# 5_cyber60-alps_periferals.net
KiCad netlist of a schematic drawn in Altium Designer
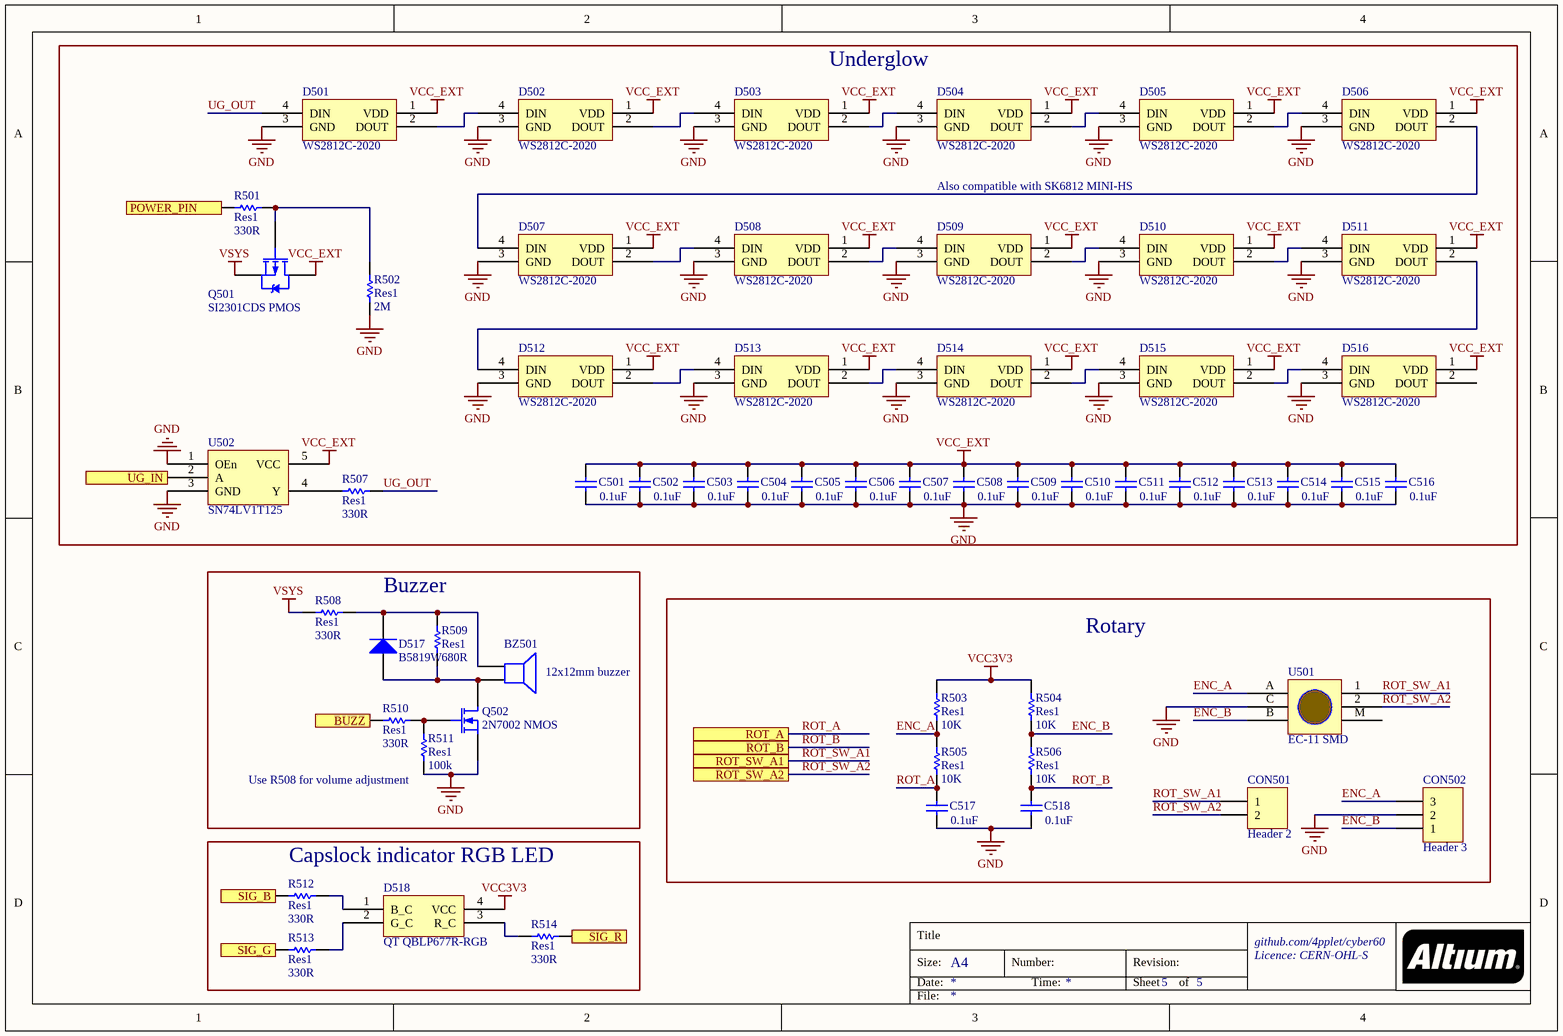
[diagram p0: 5_cyber60-alps_periferals.SchDoc]

(export (version "E")
  (design (tool "Eeschema 10.0.6"))
  (components
    (comp (ref "BZ501")
      (value "12x12mm buzzer")
      (footprint "buzzer 12x12")
      (description "Loudspeaker")
      (fields (field (name "LCSC PART #") "C409829") (field (name "MRF.PART") "YS-SBZ1230"))
      (libsource (lib "Miscellaneous Devices") (part "Speaker"))
    )
    (comp (ref "C501")
      (value "0.1uF")
      (footprint "C0603[1608]")
      (description "Capacitor")
      (fields (field (name "MFG") "KEMET") (field (name "LCSC PART #") "C14663"))
      (libsource (lib "Miscellaneous Devices") (part "Cap"))
    )
    (comp (ref "C502")
      (value "0.1uF")
      (footprint "C0603[1608]")
      (description "Capacitor")
      (fields (field (name "MFG") "KEMET") (field (name "LCSC PART #") "C14663"))
      (libsource (lib "Miscellaneous Devices") (part "Cap"))
    )
    (comp (ref "C503")
      (value "0.1uF")
      (footprint "C0603[1608]")
      (description "Capacitor")
      (fields (field (name "MFG") "KEMET") (field (name "LCSC PART #") "C14663"))
      (libsource (lib "Miscellaneous Devices") (part "Cap"))
    )
    (comp (ref "C504")
      (value "0.1uF")
      (footprint "C0603[1608]")
      (description "Capacitor")
      (fields (field (name "MFG") "KEMET") (field (name "LCSC PART #") "C14663"))
      (libsource (lib "Miscellaneous Devices") (part "Cap"))
    )
    (comp (ref "C505")
      (value "0.1uF")
      (footprint "C0603[1608]")
      (description "Capacitor")
      (fields (field (name "MFG") "KEMET") (field (name "LCSC PART #") "C14663"))
      (libsource (lib "Miscellaneous Devices") (part "Cap"))
    )
    (comp (ref "C506")
      (value "0.1uF")
      (footprint "C0603[1608]")
      (description "Capacitor")
      (fields (field (name "MFG") "KEMET") (field (name "LCSC PART #") "C14663"))
      (libsource (lib "Miscellaneous Devices") (part "Cap"))
    )
    (comp (ref "C507")
      (value "0.1uF")
      (footprint "C0603[1608]")
      (description "Capacitor")
      (fields (field (name "MFG") "KEMET") (field (name "LCSC PART #") "C14663"))
      (libsource (lib "Miscellaneous Devices") (part "Cap"))
    )
    (comp (ref "C508")
      (value "0.1uF")
      (footprint "C0603[1608]")
      (description "Capacitor")
      (fields (field (name "MFG") "KEMET") (field (name "LCSC PART #") "C14663"))
      (libsource (lib "Miscellaneous Devices") (part "Cap"))
    )
    (comp (ref "C509")
      (value "0.1uF")
      (footprint "C0603[1608]")
      (description "Capacitor")
      (fields (field (name "MFG") "KEMET") (field (name "LCSC PART #") "C14663"))
      (libsource (lib "Miscellaneous Devices") (part "Cap"))
    )
    (comp (ref "C510")
      (value "0.1uF")
      (footprint "C0603[1608]")
      (description "Capacitor")
      (fields (field (name "MFG") "KEMET") (field (name "LCSC PART #") "C14663"))
      (libsource (lib "Miscellaneous Devices") (part "Cap"))
    )
    (comp (ref "C511")
      (value "0.1uF")
      (footprint "C0603[1608]")
      (description "Capacitor")
      (fields (field (name "MFG") "KEMET") (field (name "LCSC PART #") "C14663"))
      (libsource (lib "Miscellaneous Devices") (part "Cap"))
    )
    (comp (ref "C512")
      (value "0.1uF")
      (footprint "C0603[1608]")
      (description "Capacitor")
      (fields (field (name "MFG") "KEMET") (field (name "LCSC PART #") "C14663"))
      (libsource (lib "Miscellaneous Devices") (part "Cap"))
    )
    (comp (ref "C513")
      (value "0.1uF")
      (footprint "C0603[1608]")
      (description "Capacitor")
      (fields (field (name "MFG") "KEMET") (field (name "LCSC PART #") "C14663"))
      (libsource (lib "Miscellaneous Devices") (part "Cap"))
    )
    (comp (ref "C514")
      (value "0.1uF")
      (footprint "C0603[1608]")
      (description "Capacitor")
      (fields (field (name "MFG") "KEMET") (field (name "LCSC PART #") "C14663"))
      (libsource (lib "Miscellaneous Devices") (part "Cap"))
    )
    (comp (ref "C515")
      (value "0.1uF")
      (footprint "C0603[1608]")
      (description "Capacitor")
      (fields (field (name "MFG") "KEMET") (field (name "LCSC PART #") "C14663"))
      (libsource (lib "Miscellaneous Devices") (part "Cap"))
    )
    (comp (ref "C516")
      (value "0.1uF")
      (footprint "C0603[1608]")
      (description "Capacitor")
      (fields (field (name "MFG") "KEMET") (field (name "LCSC PART #") "C14663"))
      (libsource (lib "Miscellaneous Devices") (part "Cap"))
    )
    (comp (ref "C517")
      (value "0.1uF")
      (footprint "C0603[1608]")
      (description "Capacitor")
      (fields (field (name "MFG") "KEMET") (field (name "LCSC PART #") "C14663"))
      (libsource (lib "Miscellaneous Devices") (part "Cap"))
    )
    (comp (ref "C518")
      (value "0.1uF")
      (footprint "C0603[1608]")
      (description "Capacitor")
      (fields (field (name "MFG") "KEMET") (field (name "LCSC PART #") "C14663"))
      (libsource (lib "Miscellaneous Devices") (part "Cap"))
    )
    (comp (ref "CON501")
      (value "Header 2")
      (footprint "HDR1X2")
      (description "Header, 2-Pin")
      (libsource (lib "Miscellaneous Connectors") (part "Header 2"))
    )
    (comp (ref "CON502")
      (value "Header 3")
      (footprint "HDR1X3")
      (description "Header, 3-Pin")
      (libsource (lib "Miscellaneous Connectors") (part "Header 3"))
    )
    (comp (ref "D501")
      (value "WS2812C-2020")
      (footprint "WS2812B - 2020")
      (fields (field (name "LCSC PART #") "C965556"))
      (libsource (lib "Keebs") (part "WS2812B"))
    )
    (comp (ref "D502")
      (value "WS2812C-2020")
      (footprint "WS2812B - 2020")
      (fields (field (name "LCSC PART #") "C965556"))
      (libsource (lib "Keebs") (part "WS2812B"))
    )
    (comp (ref "D503")
      (value "WS2812C-2020")
      (footprint "WS2812B - 2020")
      (fields (field (name "LCSC PART #") "C965556"))
      (libsource (lib "Keebs") (part "WS2812B"))
    )
    (comp (ref "D504")
      (value "WS2812C-2020")
      (footprint "WS2812B - 2020")
      (fields (field (name "LCSC PART #") "C965556"))
      (libsource (lib "Keebs") (part "WS2812B"))
    )
    (comp (ref "D505")
      (value "WS2812C-2020")
      (footprint "WS2812B - 2020")
      (fields (field (name "LCSC PART #") "C965556"))
      (libsource (lib "Keebs") (part "WS2812B"))
    )
    (comp (ref "D506")
      (value "WS2812C-2020")
      (footprint "WS2812B - 2020")
      (fields (field (name "LCSC PART #") "C965556"))
      (libsource (lib "Keebs") (part "WS2812B"))
    )
    (comp (ref "D507")
      (value "WS2812C-2020")
      (footprint "WS2812B - 2020")
      (fields (field (name "LCSC PART #") "C965556"))
      (libsource (lib "Keebs") (part "WS2812B"))
    )
    (comp (ref "D508")
      (value "WS2812C-2020")
      (footprint "WS2812B - 2020")
      (fields (field (name "LCSC PART #") "C965556"))
      (libsource (lib "Keebs") (part "WS2812B"))
    )
    (comp (ref "D509")
      (value "WS2812C-2020")
      (footprint "WS2812B - 2020")
      (fields (field (name "LCSC PART #") "C965556"))
      (libsource (lib "Keebs") (part "WS2812B"))
    )
    (comp (ref "D510")
      (value "WS2812C-2020")
      (footprint "WS2812B - 2020")
      (fields (field (name "LCSC PART #") "C965556"))
      (libsource (lib "Keebs") (part "WS2812B"))
    )
    (comp (ref "D511")
      (value "WS2812C-2020")
      (footprint "WS2812B - 2020")
      (fields (field (name "LCSC PART #") "C965556"))
      (libsource (lib "Keebs") (part "WS2812B"))
    )
    (comp (ref "D512")
      (value "WS2812C-2020")
      (footprint "WS2812B - 2020")
      (fields (field (name "LCSC PART #") "C965556"))
      (libsource (lib "Keebs") (part "WS2812B"))
    )
    (comp (ref "D513")
      (value "WS2812C-2020")
      (footprint "WS2812B - 2020")
      (fields (field (name "LCSC PART #") "C965556"))
      (libsource (lib "Keebs") (part "WS2812B"))
    )
    (comp (ref "D514")
      (value "WS2812C-2020")
      (footprint "WS2812B - 2020")
      (fields (field (name "LCSC PART #") "C965556"))
      (libsource (lib "Keebs") (part "WS2812B"))
    )
    (comp (ref "D515")
      (value "WS2812C-2020")
      (footprint "WS2812B - 2020")
      (fields (field (name "LCSC PART #") "C965556"))
      (libsource (lib "Keebs") (part "WS2812B"))
    )
    (comp (ref "D516")
      (value "WS2812C-2020")
      (footprint "WS2812B - 2020")
      (fields (field (name "LCSC PART #") "C965556"))
      (libsource (lib "Keebs") (part "WS2812B"))
    )
    (comp (ref "D517")
      (value "B5819W")
      (footprint "SOD-123")
      (description "Default Diode")
      (fields (field (name "LCSC PART #") "C8598"))
      (libsource (lib "Miscellaneous Devices") (part "Diode"))
    )
    (comp (ref "D518")
      (value "QT QBLP677R-RGB")
      (footprint "QT QBLP677R-RGB")
      (description "RGB LED")
      (fields (field (name "MFG") "QT Brightek (QTB)"))
      (libsource (lib "Keebs") (part "QT QBLP677R-RGB"))
    )
    (comp (ref "Q501")
      (value "SI2301CDS PMOS")
      (footprint "SOT-23-3")
      (description "P-Channel Power MOSFET")
      (fields (field (name "MRF.PART") "SI2301CDS-T1-GE3") (field (name "LCSC PART #") "C10487"))
      (libsource (lib "Miscellaneous Devices") (part "PMOS-2"))
    )
    (comp (ref "Q502")
      (value "2N7002 NMOS")
      (footprint "SOT-23-3")
      (description "N-Channel MOSFET")
      (fields (field (name "LCSC PART #") "C8545") (field (name "MRF.PART") "2N7002"))
      (libsource (lib "Miscellaneous Devices") (part "MOSFET-N"))
    )
    (comp (ref "R501")
      (value "Res1")
      (footprint "R0603[1608]")
      (description "Resistor")
      (fields
        (field (name "ALTIUM_VALUE") "330R")
        (field (name "LCSC PART #") "C23138")
        (field (name "MRF.PART") "0603WAF3300T5E")
      )
      (libsource (lib "Miscellaneous Devices") (part "Res1"))
    )
    (comp (ref "R502")
      (value "Res1")
      (footprint "R0603[1608]")
      (description "Resistor")
      (fields
        (field (name "ALTIUM_VALUE") "2M")
        (field (name "MRF.PART") "0603WAF2004T5E")
        (field (name "LCSC PART #") "C22976")
      )
      (libsource (lib "Miscellaneous Devices") (part "Res1"))
    )
    (comp (ref "R503")
      (value "Res1")
      (footprint "R0603[1608]")
      (description "Resistor")
      (fields
        (field (name "ALTIUM_VALUE") "10K")
        (field (name "MRF.PART") "0603WAF1002T5E")
        (field (name "LCSC PART #") "C25804")
      )
      (libsource (lib "Miscellaneous Devices") (part "Res1"))
    )
    (comp (ref "R504")
      (value "Res1")
      (footprint "R0603[1608]")
      (description "Resistor")
      (fields
        (field (name "ALTIUM_VALUE") "10K")
        (field (name "MRF.PART") "0603WAF1002T5E")
        (field (name "LCSC PART #") "C25804")
      )
      (libsource (lib "Miscellaneous Devices") (part "Res1"))
    )
    (comp (ref "R505")
      (value "Res1")
      (footprint "R0603[1608]")
      (description "Resistor")
      (fields
        (field (name "ALTIUM_VALUE") "10K")
        (field (name "MRF.PART") "0603WAF1002T5E")
        (field (name "LCSC PART #") "C25804")
      )
      (libsource (lib "Miscellaneous Devices") (part "Res1"))
    )
    (comp (ref "R506")
      (value "Res1")
      (footprint "R0603[1608]")
      (description "Resistor")
      (fields
        (field (name "ALTIUM_VALUE") "10K")
        (field (name "MRF.PART") "0603WAF1002T5E")
        (field (name "LCSC PART #") "C25804")
      )
      (libsource (lib "Miscellaneous Devices") (part "Res1"))
    )
    (comp (ref "R507")
      (value "Res1")
      (footprint "R0603[1608]")
      (description "Resistor")
      (fields
        (field (name "ALTIUM_VALUE") "330R")
        (field (name "LCSC PART #") "C23138")
        (field (name "MRF.PART") "0603WAF3300T5E")
      )
      (libsource (lib "Miscellaneous Devices") (part "Res1"))
    )
    (comp (ref "R508")
      (value "Res1")
      (footprint "R0603[1608]")
      (description "Resistor")
      (fields
        (field (name "ALTIUM_VALUE") "330R")
        (field (name "LCSC PART #") "C23138")
        (field (name "MRF.PART") "0603WAF3300T5E")
      )
      (libsource (lib "Miscellaneous Devices") (part "Res1"))
    )
    (comp (ref "R509")
      (value "Res1")
      (footprint "R0603[1608]")
      (description "Resistor")
      (fields
        (field (name "ALTIUM_VALUE") "680R")
        (field (name "MRF.PART") "0603WAF6800T5E")
        (field (name "LCSC PART #") "C23228")
      )
      (libsource (lib "Miscellaneous Devices") (part "Res1"))
    )
    (comp (ref "R510")
      (value "Res1")
      (footprint "R0603[1608]")
      (description "Resistor")
      (fields
        (field (name "ALTIUM_VALUE") "330R")
        (field (name "LCSC PART #") "C23138")
        (field (name "MRF.PART") "0603WAF3300T5E")
      )
      (libsource (lib "Miscellaneous Devices") (part "Res1"))
    )
    (comp (ref "R511")
      (value "Res1")
      (footprint "R0603[1608]")
      (description "Resistor")
      (fields
        (field (name "ALTIUM_VALUE") "100k")
        (field (name "MRF.PART") "0603WAF1003T5E")
        (field (name "LCSC PART #") "C25803")
      )
      (libsource (lib "Miscellaneous Devices") (part "Res1"))
    )
    (comp (ref "R512")
      (value "Res1")
      (footprint "R0603[1608]")
      (description "Resistor")
      (fields
        (field (name "ALTIUM_VALUE") "330R")
        (field (name "LCSC PART #") "C23138")
        (field (name "MRF.PART") "0603WAF3300T5E")
      )
      (libsource (lib "Miscellaneous Devices") (part "Res1"))
    )
    (comp (ref "R513")
      (value "Res1")
      (footprint "R0603[1608]")
      (description "Resistor")
      (fields
        (field (name "ALTIUM_VALUE") "330R")
        (field (name "LCSC PART #") "C23138")
        (field (name "MRF.PART") "0603WAF3300T5E")
      )
      (libsource (lib "Miscellaneous Devices") (part "Res1"))
    )
    (comp (ref "R514")
      (value "Res1")
      (footprint "R0603[1608]")
      (description "Resistor")
      (fields
        (field (name "ALTIUM_VALUE") "330R")
        (field (name "LCSC PART #") "C23138")
        (field (name "MRF.PART") "0603WAF3300T5E")
      )
      (libsource (lib "Miscellaneous Devices") (part "Res1"))
    )
    (comp (ref "U501") (value "EC-11 SMD") (footprint "EC11-SMD") (libsource (lib "Keebs") (part "EC-11")))
    (comp (ref "U502")
      (value "SN74LV1T125")
      (footprint "SOT-23-5")
      (description "SN74LV1T125 or SN74LV1T34. Connect OE to GND")
      (fields (field (name "LCSC PART #") "C473338") (field (name "MRF.PART") "SN74LV1T125DBVR"))
      (libsource (lib "Keebs") (part "SN74LV1T125"))
    )
  )
  (nets
    (net (code "1") (name "/BUZZ") (class "Default")
      (node (ref "R510") (pin "2") (pinfunction "2_2") (pintype "passive"))
    )
    (net (code "2") (name "/ENC_A") (class "Default")
      (node (ref "CON502") (pin "3") (pinfunction "3_3") (pintype "passive"))
      (node (ref "R503") (pin "2") (pinfunction "2_2") (pintype "passive"))
      (node (ref "R505") (pin "1") (pinfunction "1_1") (pintype "passive"))
      (node (ref "U501") (pin "A") (pinfunction "B_A") (pintype "passive"))
    )
    (net (code "3") (name "/ENC_B") (class "Default")
      (node (ref "CON502") (pin "1") (pinfunction "1_1") (pintype "passive"))
      (node (ref "R504") (pin "2") (pinfunction "2_2") (pintype "passive"))
      (node (ref "R506") (pin "1") (pinfunction "1_1") (pintype "passive"))
      (node (ref "U501") (pin "B") (pinfunction "B_B") (pintype "passive"))
    )
    (net (code "4") (name "/POWER_PIN") (class "Default")
      (node (ref "R501") (pin "1") (pinfunction "1_1") (pintype "passive"))
    )
    (net (code "5") (name "/ROT_A") (class "Default")
      (node (ref "C517") (pin "2") (pinfunction "2_2") (pintype "passive"))
      (node (ref "R505") (pin "2") (pinfunction "2_2") (pintype "passive"))
    )
    (net (code "6") (name "/ROT_B") (class "Default")
      (node (ref "C518") (pin "2") (pinfunction "2_2") (pintype "passive"))
      (node (ref "R506") (pin "2") (pinfunction "2_2") (pintype "passive"))
    )
    (net (code "7") (name "/ROT_SW_A1") (class "Default")
      (node (ref "CON501") (pin "1") (pinfunction "1_1") (pintype "passive"))
      (node (ref "U501") (pin "1") (pinfunction "1_1") (pintype "passive"))
    )
    (net (code "8") (name "/ROT_SW_A2") (class "Default")
      (node (ref "CON501") (pin "2") (pinfunction "2_2") (pintype "passive"))
      (node (ref "U501") (pin "2") (pinfunction "2_2") (pintype "passive"))
    )
    (net (code "9") (name "/SIG_B") (class "Default")
      (node (ref "R512") (pin "2") (pinfunction "2_2") (pintype "passive"))
    )
    (net (code "10") (name "/SIG_G") (class "Default")
      (node (ref "R513") (pin "2") (pinfunction "2_2") (pintype "passive"))
    )
    (net (code "11") (name "/SIG_R") (class "Default")
      (node (ref "R514") (pin "1") (pinfunction "1_1") (pintype "passive"))
    )
    (net (code "12") (name "/UG_IN") (class "Default")
      (node (ref "U502") (pin "2") (pinfunction "A_2") (pintype "passive"))
    )
    (net (code "13") (name "/UG_OUT") (class "Default")
      (node (ref "D501") (pin "4") (pinfunction "DIN_4") (pintype "passive"))
      (node (ref "R507") (pin "1") (pinfunction "1_1") (pintype "passive"))
    )
    (net (code "14") (name "GND") (class "Default")
      (node (ref "C501") (pin "1") (pinfunction "1_1") (pintype "passive"))
      (node (ref "C502") (pin "1") (pinfunction "1_1") (pintype "passive"))
      (node (ref "C503") (pin "1") (pinfunction "1_1") (pintype "passive"))
      (node (ref "C504") (pin "1") (pinfunction "1_1") (pintype "passive"))
      (node (ref "C505") (pin "1") (pinfunction "1_1") (pintype "passive"))
      (node (ref "C506") (pin "1") (pinfunction "1_1") (pintype "passive"))
      (node (ref "C507") (pin "1") (pinfunction "1_1") (pintype "passive"))
      (node (ref "C508") (pin "1") (pinfunction "1_1") (pintype "passive"))
      (node (ref "C509") (pin "1") (pinfunction "1_1") (pintype "passive"))
      (node (ref "C510") (pin "1") (pinfunction "1_1") (pintype "passive"))
      (node (ref "C511") (pin "1") (pinfunction "1_1") (pintype "passive"))
      (node (ref "C512") (pin "1") (pinfunction "1_1") (pintype "passive"))
      (node (ref "C513") (pin "1") (pinfunction "1_1") (pintype "passive"))
      (node (ref "C514") (pin "1") (pinfunction "1_1") (pintype "passive"))
      (node (ref "C515") (pin "1") (pinfunction "1_1") (pintype "passive"))
      (node (ref "C516") (pin "1") (pinfunction "1_1") (pintype "passive"))
      (node (ref "C517") (pin "1") (pinfunction "1_1") (pintype "passive"))
      (node (ref "C518") (pin "1") (pinfunction "1_1") (pintype "passive"))
      (node (ref "CON502") (pin "2") (pinfunction "2_2") (pintype "passive"))
      (node (ref "D501") (pin "3") (pinfunction "GND_3") (pintype "passive"))
      (node (ref "D502") (pin "3") (pinfunction "GND_3") (pintype "passive"))
      (node (ref "D503") (pin "3") (pinfunction "GND_3") (pintype "passive"))
      (node (ref "D504") (pin "3") (pinfunction "GND_3") (pintype "passive"))
      (node (ref "D505") (pin "3") (pinfunction "GND_3") (pintype "passive"))
      (node (ref "D506") (pin "3") (pinfunction "GND_3") (pintype "passive"))
      (node (ref "D507") (pin "3") (pinfunction "GND_3") (pintype "passive"))
      (node (ref "D508") (pin "3") (pinfunction "GND_3") (pintype "passive"))
      (node (ref "D509") (pin "3") (pinfunction "GND_3") (pintype "passive"))
      (node (ref "D510") (pin "3") (pinfunction "GND_3") (pintype "passive"))
      (node (ref "D511") (pin "3") (pinfunction "GND_3") (pintype "passive"))
      (node (ref "D512") (pin "3") (pinfunction "GND_3") (pintype "passive"))
      (node (ref "D513") (pin "3") (pinfunction "GND_3") (pintype "passive"))
      (node (ref "D514") (pin "3") (pinfunction "GND_3") (pintype "passive"))
      (node (ref "D515") (pin "3") (pinfunction "GND_3") (pintype "passive"))
      (node (ref "D516") (pin "3") (pinfunction "GND_3") (pintype "passive"))
      (node (ref "Q502") (pin "2") (pinfunction "S_2") (pintype "passive"))
      (node (ref "R502") (pin "1") (pinfunction "1_1") (pintype "passive"))
      (node (ref "R511") (pin "2") (pinfunction "2_2") (pintype "passive"))
      (node (ref "U501") (pin "C") (pinfunction "C_C") (pintype "passive"))
      (node (ref "U502") (pin "1") (pinfunction "OEn_1") (pintype "passive"))
      (node (ref "U502") (pin "3") (pinfunction "GND_3") (pintype "passive"))
    )
    (net (code "15") (name "Net-(D501-DOUT)") (class "Default")
      (node (ref "D501") (pin "2") (pinfunction "DOUT_2") (pintype "passive"))
      (node (ref "D502") (pin "4") (pinfunction "DIN_4") (pintype "passive"))
    )
    (net (code "16") (name "Net-(D502-DOUT)") (class "Default")
      (node (ref "D502") (pin "2") (pinfunction "DOUT_2") (pintype "passive"))
      (node (ref "D503") (pin "4") (pinfunction "DIN_4") (pintype "passive"))
    )
    (net (code "17") (name "Net-(D503-DOUT)") (class "Default")
      (node (ref "D503") (pin "2") (pinfunction "DOUT_2") (pintype "passive"))
      (node (ref "D504") (pin "4") (pinfunction "DIN_4") (pintype "passive"))
    )
    (net (code "18") (name "Net-(D504-DOUT)") (class "Default")
      (node (ref "D504") (pin "2") (pinfunction "DOUT_2") (pintype "passive"))
      (node (ref "D505") (pin "4") (pinfunction "DIN_4") (pintype "passive"))
    )
    (net (code "19") (name "Net-(D505-DOUT)") (class "Default")
      (node (ref "D505") (pin "2") (pinfunction "DOUT_2") (pintype "passive"))
      (node (ref "D506") (pin "4") (pinfunction "DIN_4") (pintype "passive"))
    )
    (net (code "20") (name "Net-(D506-DOUT)") (class "Default")
      (node (ref "D506") (pin "2") (pinfunction "DOUT_2") (pintype "passive"))
      (node (ref "D507") (pin "4") (pinfunction "DIN_4") (pintype "passive"))
    )
    (net (code "21") (name "Net-(D507-DOUT)") (class "Default")
      (node (ref "D507") (pin "2") (pinfunction "DOUT_2") (pintype "passive"))
      (node (ref "D508") (pin "4") (pinfunction "DIN_4") (pintype "passive"))
    )
    (net (code "22") (name "Net-(D508-DOUT)") (class "Default")
      (node (ref "D508") (pin "2") (pinfunction "DOUT_2") (pintype "passive"))
      (node (ref "D509") (pin "4") (pinfunction "DIN_4") (pintype "passive"))
    )
    (net (code "23") (name "Net-(D509-DOUT)") (class "Default")
      (node (ref "D509") (pin "2") (pinfunction "DOUT_2") (pintype "passive"))
      (node (ref "D510") (pin "4") (pinfunction "DIN_4") (pintype "passive"))
    )
    (net (code "24") (name "Net-(D510-DOUT)") (class "Default")
      (node (ref "D510") (pin "2") (pinfunction "DOUT_2") (pintype "passive"))
      (node (ref "D511") (pin "4") (pinfunction "DIN_4") (pintype "passive"))
    )
    (net (code "25") (name "Net-(D511-DOUT)") (class "Default")
      (node (ref "D511") (pin "2") (pinfunction "DOUT_2") (pintype "passive"))
      (node (ref "D512") (pin "4") (pinfunction "DIN_4") (pintype "passive"))
    )
    (net (code "26") (name "Net-(D512-DOUT)") (class "Default")
      (node (ref "D512") (pin "2") (pinfunction "DOUT_2") (pintype "passive"))
      (node (ref "D513") (pin "4") (pinfunction "DIN_4") (pintype "passive"))
    )
    (net (code "27") (name "Net-(D513-DOUT)") (class "Default")
      (node (ref "D513") (pin "2") (pinfunction "DOUT_2") (pintype "passive"))
      (node (ref "D514") (pin "4") (pinfunction "DIN_4") (pintype "passive"))
    )
    (net (code "28") (name "Net-(D514-DOUT)") (class "Default")
      (node (ref "D514") (pin "2") (pinfunction "DOUT_2") (pintype "passive"))
      (node (ref "D515") (pin "4") (pinfunction "DIN_4") (pintype "passive"))
    )
    (net (code "29") (name "Net-(D515-DOUT)") (class "Default")
      (node (ref "D515") (pin "2") (pinfunction "DOUT_2") (pintype "passive"))
      (node (ref "D516") (pin "4") (pinfunction "DIN_4") (pintype "passive"))
    )
    (net (code "30") (name "Net-(D517-A)") (class "Default")
      (node (ref "BZ501") (pin "2") (pinfunction "2_2") (pintype "passive"))
      (node (ref "D517") (pin "1") (pinfunction "A_1") (pintype "passive"))
      (node (ref "Q502") (pin "3") (pinfunction "D_3") (pintype "passive"))
      (node (ref "R509") (pin "2") (pinfunction "2_2") (pintype "passive"))
    )
    (net (code "31") (name "Net-(D517-K)") (class "Default")
      (node (ref "BZ501") (pin "1") (pinfunction "1_1") (pintype "passive"))
      (node (ref "D517") (pin "2") (pinfunction "K_2") (pintype "passive"))
      (node (ref "R508") (pin "1") (pinfunction "1_1") (pintype "passive"))
      (node (ref "R509") (pin "1") (pinfunction "1_1") (pintype "passive"))
    )
    (net (code "32") (name "Net-(D518-B_C)") (class "Default")
      (node (ref "D518") (pin "1") (pinfunction "B_C_1") (pintype "passive"))
      (node (ref "R512") (pin "1") (pinfunction "1_1") (pintype "passive"))
    )
    (net (code "33") (name "Net-(D518-G_C)") (class "Default")
      (node (ref "D518") (pin "2") (pinfunction "G_C_2") (pintype "passive"))
      (node (ref "R513") (pin "1") (pinfunction "1_1") (pintype "passive"))
    )
    (net (code "34") (name "Net-(D518-R_C)") (class "Default")
      (node (ref "D518") (pin "3") (pinfunction "R_C_3") (pintype "passive"))
      (node (ref "R514") (pin "2") (pinfunction "2_2") (pintype "passive"))
    )
    (net (code "35") (name "Net-(Q501-G)") (class "Default")
      (node (ref "Q501") (pin "1") (pinfunction "G_1") (pintype "passive"))
      (node (ref "R501") (pin "2") (pinfunction "2_2") (pintype "passive"))
      (node (ref "R502") (pin "2") (pinfunction "2_2") (pintype "passive"))
    )
    (net (code "36") (name "Net-(Q502-G)") (class "Default")
      (node (ref "Q502") (pin "1") (pinfunction "G_1") (pintype "passive"))
      (node (ref "R510") (pin "1") (pinfunction "1_1") (pintype "passive"))
      (node (ref "R511") (pin "1") (pinfunction "1_1") (pintype "passive"))
    )
    (net (code "37") (name "Net-(U502-Y)") (class "Default")
      (node (ref "R507") (pin "2") (pinfunction "2_2") (pintype "passive"))
      (node (ref "U502") (pin "4") (pinfunction "Y_4") (pintype "passive"))
    )
    (net (code "38") (name "VCC3V3") (class "Default")
      (node (ref "D518") (pin "4") (pinfunction "VCC_4") (pintype "passive"))
      (node (ref "R503") (pin "1") (pinfunction "1_1") (pintype "passive"))
      (node (ref "R504") (pin "1") (pinfunction "1_1") (pintype "passive"))
    )
    (net (code "39") (name "VCC_EXT") (class "Default")
      (node (ref "C501") (pin "2") (pinfunction "2_2") (pintype "passive"))
      (node (ref "C502") (pin "2") (pinfunction "2_2") (pintype "passive"))
      (node (ref "C503") (pin "2") (pinfunction "2_2") (pintype "passive"))
      (node (ref "C504") (pin "2") (pinfunction "2_2") (pintype "passive"))
      (node (ref "C505") (pin "2") (pinfunction "2_2") (pintype "passive"))
      (node (ref "C506") (pin "2") (pinfunction "2_2") (pintype "passive"))
      (node (ref "C507") (pin "2") (pinfunction "2_2") (pintype "passive"))
      (node (ref "C508") (pin "2") (pinfunction "2_2") (pintype "passive"))
      (node (ref "C509") (pin "2") (pinfunction "2_2") (pintype "passive"))
      (node (ref "C510") (pin "2") (pinfunction "2_2") (pintype "passive"))
      (node (ref "C511") (pin "2") (pinfunction "2_2") (pintype "passive"))
      (node (ref "C512") (pin "2") (pinfunction "2_2") (pintype "passive"))
      (node (ref "C513") (pin "2") (pinfunction "2_2") (pintype "passive"))
      (node (ref "C514") (pin "2") (pinfunction "2_2") (pintype "passive"))
      (node (ref "C515") (pin "2") (pinfunction "2_2") (pintype "passive"))
      (node (ref "C516") (pin "2") (pinfunction "2_2") (pintype "passive"))
      (node (ref "D501") (pin "1") (pinfunction "VDD_1") (pintype "passive"))
      (node (ref "D502") (pin "1") (pinfunction "VDD_1") (pintype "passive"))
      (node (ref "D503") (pin "1") (pinfunction "VDD_1") (pintype "passive"))
      (node (ref "D504") (pin "1") (pinfunction "VDD_1") (pintype "passive"))
      (node (ref "D505") (pin "1") (pinfunction "VDD_1") (pintype "passive"))
      (node (ref "D506") (pin "1") (pinfunction "VDD_1") (pintype "passive"))
      (node (ref "D507") (pin "1") (pinfunction "VDD_1") (pintype "passive"))
      (node (ref "D508") (pin "1") (pinfunction "VDD_1") (pintype "passive"))
      (node (ref "D509") (pin "1") (pinfunction "VDD_1") (pintype "passive"))
      (node (ref "D510") (pin "1") (pinfunction "VDD_1") (pintype "passive"))
      (node (ref "D511") (pin "1") (pinfunction "VDD_1") (pintype "passive"))
      (node (ref "D512") (pin "1") (pinfunction "VDD_1") (pintype "passive"))
      (node (ref "D513") (pin "1") (pinfunction "VDD_1") (pintype "passive"))
      (node (ref "D514") (pin "1") (pinfunction "VDD_1") (pintype "passive"))
      (node (ref "D515") (pin "1") (pinfunction "VDD_1") (pintype "passive"))
      (node (ref "D516") (pin "1") (pinfunction "VDD_1") (pintype "passive"))
      (node (ref "Q501") (pin "3") (pinfunction "D_3") (pintype "passive"))
      (node (ref "U502") (pin "5") (pinfunction "VCC_5") (pintype "passive"))
    )
    (net (code "40") (name "VSYS") (class "Default")
      (node (ref "Q501") (pin "2") (pinfunction "S_2") (pintype "passive"))
      (node (ref "R508") (pin "2") (pinfunction "2_2") (pintype "passive"))
    )
    (net (code "41") (name "unconnected-(D516-DOUT-Pad2)") (class "Default")
      (node (ref "D516") (pin "2") (pinfunction "DOUT_2") (pintype "passive"))
    )
    (net (code "42") (name "unconnected-(U501-PadM)") (class "Default")
      (node (ref "U501") (pin "M") (pinfunction "M_M") (pintype "passive"))
    )
  )
)
